# spi_can_controller.net
KiCad netlist of a schematic drawn in Altium Designer
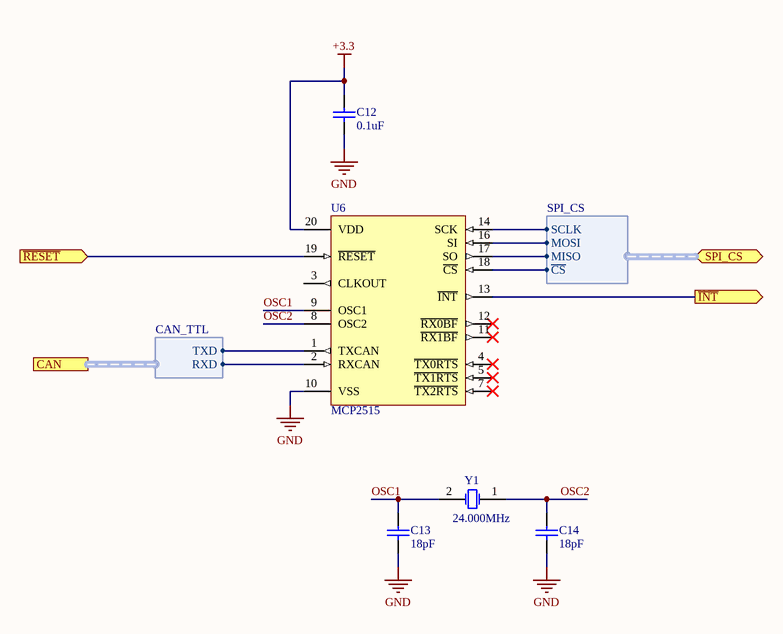
[diagram p0: spi can controller.SchDoc]

(export (version "E")
  (design (tool "Eeschema 10.0.6"))
  (components
    (comp (ref "C12")
      (value "0.1uF")
      (footprint "C0603")
      (description "Capacitor")
      (fields (field (name "Comment") "Cap"))
      (libsource (lib "Miscellaneous Devices") (part "Cap"))
    )
    (comp (ref "C13")
      (value "18pF")
      (footprint "C0603")
      (description "Capacitor")
      (fields (field (name "Comment") "Cap"))
      (libsource (lib "Miscellaneous Devices") (part "Cap"))
    )
    (comp (ref "C14")
      (value "18pF")
      (footprint "C0603")
      (description "Capacitor")
      (fields (field (name "Comment") "Cap"))
      (libsource (lib "Miscellaneous Devices") (part "Cap"))
    )
    (comp (ref "U6")
      (value "MCP2515")
      (footprint "MCP2515")
      (description "MICROCHIP - MCP2515-I/ST - CAN CONTROLLER, SMD, 2515, TSSOP20")
      (libsource (lib "MCP2515") (part "MCP2515"))
    )
    (comp (ref "Y1")
      (value "24.000MHz")
      (footprint "C3E-24.000-12-3030-X")
      (description "Crystal Oscillator")
      (fields (field (name "Comment") "XTAL"))
      (libsource (lib "Miscellaneous Devices") (part "XTAL"))
    )
  )
  (nets
    (net (code "3") (name "+3.3") (class "Default")
      (node (ref "C12") (pin "1") (pinfunction "1_1") (pintype "passive"))
      (node (ref "U6") (pin "20") (pinfunction "VDD_20") (pintype "power_in"))
    )
    (net (code "4") (name "/MISO") (class "Default")
      (node (ref "U6") (pin "17") (pinfunction "SO_17") (pintype "output"))
    )
    (net (code "5") (name "/MOSI") (class "Default")
      (node (ref "U6") (pin "16") (pinfunction "SI_16") (pintype "input"))
    )
    (net (code "6") (name "/OSC1") (class "Default")
      (node (ref "C13") (pin "1") (pinfunction "1_1") (pintype "passive"))
      (node (ref "U6") (pin "9") (pinfunction "OSC1_9") (pintype "passive"))
      (node (ref "Y1") (pin "2") (pinfunction "OSC2_2") (pintype "passive"))
    )
    (net (code "7") (name "/OSC2") (class "Default")
      (node (ref "C14") (pin "1") (pinfunction "1_1") (pintype "passive"))
      (node (ref "U6") (pin "8") (pinfunction "OSC2_8") (pintype "passive"))
      (node (ref "Y1") (pin "1") (pinfunction "OSC1_1") (pintype "passive"))
    )
    (net (code "8") (name "/RXD") (class "Default")
      (node (ref "U6") (pin "2") (pinfunction "RXCAN_2") (pintype "input"))
    )
    (net (code "9") (name "/SCLK") (class "Default")
      (node (ref "U6") (pin "14") (pinfunction "SCK_14") (pintype "input"))
    )
    (net (code "10") (name "/TXD") (class "Default")
      (node (ref "U6") (pin "1") (pinfunction "TXCAN_1") (pintype "output"))
    )
    (net (code "13") (name "/~{CS}") (class "Default")
      (node (ref "U6") (pin "18") (pinfunction "~{CS}_18") (pintype "input"))
    )
    (net (code "14") (name "/~{INT}") (class "Default")
      (node (ref "U6") (pin "13") (pinfunction "~{INT}_13") (pintype "output"))
    )
    (net (code "15") (name "/~{RESET}") (class "Default")
      (node (ref "U6") (pin "19") (pinfunction "~{RESET}_19") (pintype "input"))
    )
    (net (code "16") (name "GND") (class "Default")
      (node (ref "C12") (pin "2") (pinfunction "2_2") (pintype "passive"))
      (node (ref "C13") (pin "2") (pinfunction "2_2") (pintype "passive"))
      (node (ref "C14") (pin "2") (pinfunction "2_2") (pintype "passive"))
      (node (ref "U6") (pin "10") (pinfunction "VSS_10") (pintype "power_in"))
    )
    (net (code "17") (name "unconnected-(U6-CLKOUT-Pad3)") (class "Default")
      (node (ref "U6") (pin "3") (pinfunction "CLKOUT_3") (pintype "output"))
    )
    (net (code "18") (name "unconnected-(U6-~{RX0BF}-Pad12)") (class "Default")
      (node (ref "U6") (pin "12") (pinfunction "~{RX0BF}_12") (pintype "output+no_connect"))
    )
    (net (code "19") (name "unconnected-(U6-~{RX1BF}-Pad11)") (class "Default")
      (node (ref "U6") (pin "11") (pinfunction "~{RX1BF}_11") (pintype "output+no_connect"))
    )
    (net (code "20") (name "unconnected-(U6-~{TX0RTS}-Pad4)") (class "Default")
      (node (ref "U6") (pin "4") (pinfunction "~{TX0RTS}_4") (pintype "input+no_connect"))
    )
    (net (code "21") (name "unconnected-(U6-~{TX1RTS}-Pad5)") (class "Default")
      (node (ref "U6") (pin "5") (pinfunction "~{TX1RTS}_5") (pintype "input+no_connect"))
    )
    (net (code "22") (name "unconnected-(U6-~{TX2RTS}-Pad7)") (class "Default")
      (node (ref "U6") (pin "7") (pinfunction "~{TX2RTS}_7") (pintype "input+no_connect"))
    )
  )
)
